# Schamatic.net
KiCad netlist of a schematic drawn in EAGLE
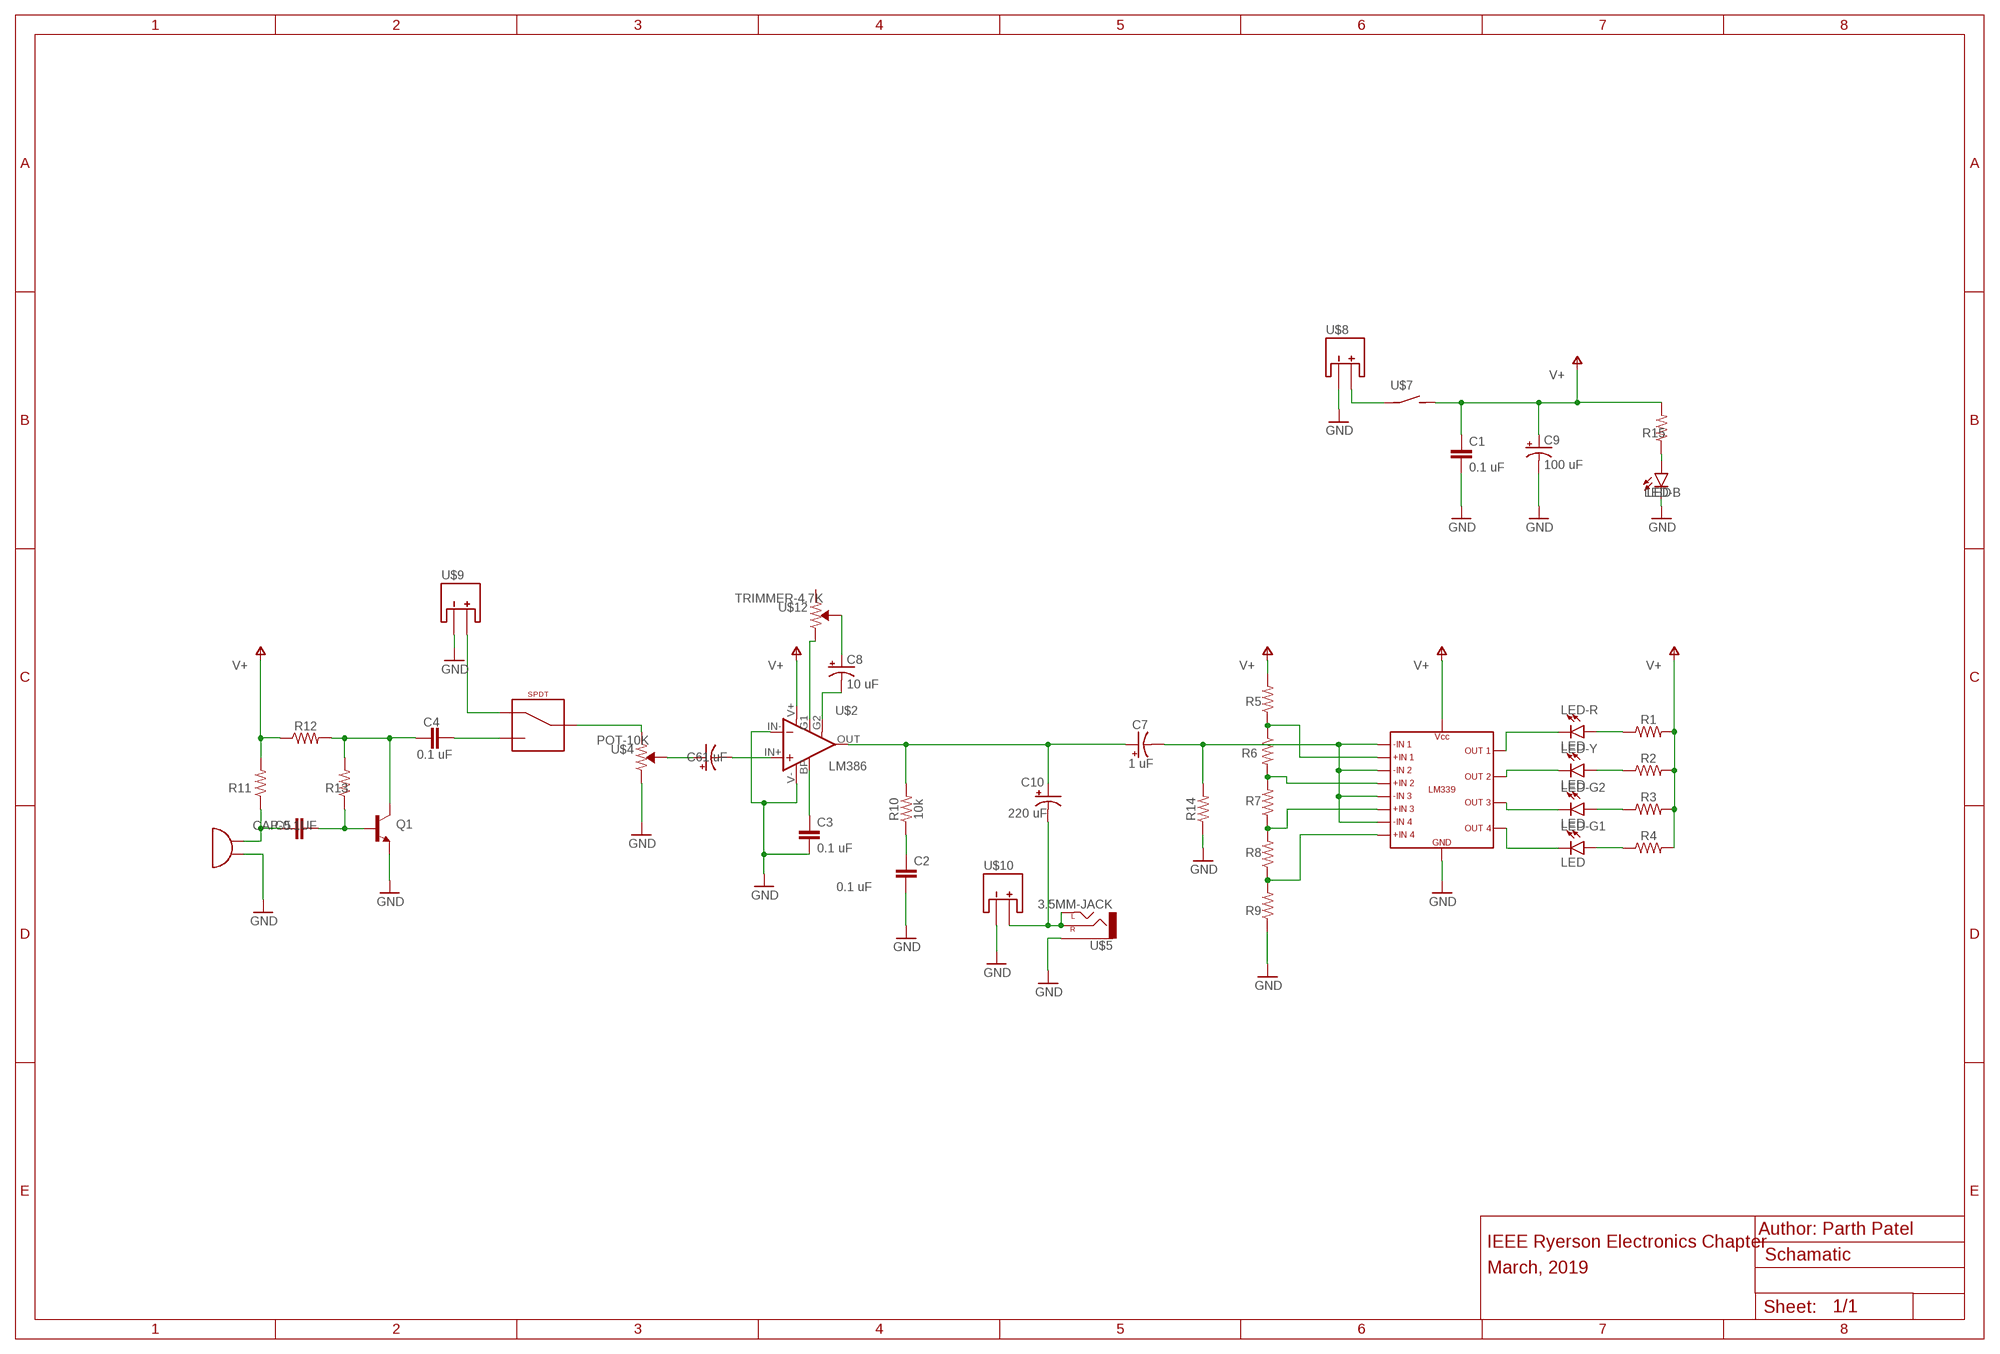
[diagram p0: schematic, sheet 1]

(export (version "E")
  (design (tool "Eeschema 10.0.6"))
  (components
    (comp (ref "C1")
      (value "0.1 uF")
      (footprint "eagle-import:CAP-PTH-SMALL-KIT")
      (libsource (lib "eagle-import") (part "CAP-0.1UF"))
    )
    (comp (ref "C2")
      (value "0.1 uF")
      (footprint "eagle-import:CAP-PTH-SMALL-KIT")
      (libsource (lib "eagle-import") (part "CAP-0.1UF"))
    )
    (comp (ref "C3")
      (value "0.1 uF")
      (footprint "eagle-import:CAP-PTH-SMALL-KIT")
      (libsource (lib "eagle-import") (part "CAP-0.1UF"))
    )
    (comp (ref "C4")
      (value "0.1 uF")
      (footprint "eagle-import:CAP-PTH-SMALL-KIT")
      (libsource (lib "eagle-import") (part "CAP-0.1UF"))
    )
    (comp (ref "C5")
      (value "CAP-0.1UF")
      (footprint "eagle-import:CAP-PTH-SMALL-KIT")
      (libsource (lib "eagle-import") (part "CAP-0.1UF"))
    )
    (comp (ref "C6")
      (value "1 uF")
      (footprint "eagle-import:CPOL-RADIAL-2.5MM-5.2MM")
      (libsource (lib "eagle-import") (part "CAP-1UF"))
    )
    (comp (ref "C7")
      (value "1 uF")
      (footprint "eagle-import:CPOL-RADIAL-2.5MM-5.2MM")
      (libsource (lib "eagle-import") (part "CAP-1UF"))
    )
    (comp (ref "C8")
      (value "10 uF")
      (footprint "eagle-import:CPOL-RADIAL-2.5MM-5.2MM")
      (libsource (lib "eagle-import") (part "CAP-10UF"))
    )
    (comp (ref "C9")
      (value "100 uF")
      (footprint "eagle-import:CPOL-RADIAL-2.5MM-6.5MM")
      (libsource (lib "eagle-import") (part "CAP-100UF"))
    )
    (comp (ref "C10")
      (value "220 uF")
      (footprint "eagle-import:CPOL-RADIAL-2.5MM-8.1MM")
      (libsource (lib "eagle-import") (part "CAP-220UF"))
    )
    (comp (ref "LED-B")
      (value "LED")
      (footprint "eagle-import:LED_5MM-KIT")
      (libsource (lib "eagle-import") (part "LED"))
    )
    (comp (ref "LED-G1")
      (value "LED")
      (footprint "eagle-import:LED_5MM-KIT")
      (libsource (lib "eagle-import") (part "LED"))
    )
    (comp (ref "LED-G2")
      (value "LED")
      (footprint "eagle-import:LED_5MM-KIT")
      (libsource (lib "eagle-import") (part "LED"))
    )
    (comp (ref "LED-R")
      (value "LED")
      (footprint "eagle-import:LED_5MM-KIT")
      (libsource (lib "eagle-import") (part "LED"))
    )
    (comp (ref "LED-Y")
      (value "LED")
      (footprint "eagle-import:LED_5MM-KIT")
      (libsource (lib "eagle-import") (part "LED"))
    )
    (comp (ref "Q1")
      (value "2N3904")
      (footprint "eagle-import:TO92-CBE")
      (libsource (lib "eagle-import") (part "2N3904"))
    )
    (comp (ref "R1")
      (value "470")
      (footprint "eagle-import:AXIAL-0.3-KIT")
      (libsource (lib "eagle-import") (part "RESISTOR"))
    )
    (comp (ref "R2")
      (value "RESISTOR")
      (footprint "eagle-import:AXIAL-0.3-KIT")
      (libsource (lib "eagle-import") (part "RESISTOR"))
    )
    (comp (ref "R3")
      (value "RESISTOR")
      (footprint "eagle-import:AXIAL-0.3-KIT")
      (libsource (lib "eagle-import") (part "RESISTOR"))
    )
    (comp (ref "R4")
      (value "RESISTOR")
      (footprint "eagle-import:AXIAL-0.3-KIT")
      (libsource (lib "eagle-import") (part "RESISTOR"))
    )
    (comp (ref "R5")
      (value "RESISTOR")
      (footprint "eagle-import:AXIAL-0.3-KIT")
      (libsource (lib "eagle-import") (part "RESISTOR"))
    )
    (comp (ref "R6")
      (value "RESISTOR")
      (footprint "eagle-import:AXIAL-0.3-KIT")
      (libsource (lib "eagle-import") (part "RESISTOR"))
    )
    (comp (ref "R7")
      (value "RESISTOR")
      (footprint "eagle-import:AXIAL-0.3-KIT")
      (libsource (lib "eagle-import") (part "RESISTOR"))
    )
    (comp (ref "R8")
      (value "RESISTOR")
      (footprint "eagle-import:AXIAL-0.3-KIT")
      (libsource (lib "eagle-import") (part "RESISTOR"))
    )
    (comp (ref "R9")
      (value "RESISTOR")
      (footprint "eagle-import:AXIAL-0.3-KIT")
      (libsource (lib "eagle-import") (part "RESISTOR"))
    )
    (comp (ref "R10")
      (value "10k")
      (footprint "eagle-import:AXIAL-0.3-KIT")
      (libsource (lib "eagle-import") (part "RESISTOR"))
    )
    (comp (ref "R11")
      (value "RESISTOR")
      (footprint "eagle-import:AXIAL-0.3-KIT")
      (libsource (lib "eagle-import") (part "RESISTOR"))
    )
    (comp (ref "R12")
      (value "RESISTOR")
      (footprint "eagle-import:AXIAL-0.3-KIT")
      (libsource (lib "eagle-import") (part "RESISTOR"))
    )
    (comp (ref "R13")
      (value "RESISTOR")
      (footprint "eagle-import:AXIAL-0.3-KIT")
      (libsource (lib "eagle-import") (part "RESISTOR"))
    )
    (comp (ref "R14")
      (value "RESISTOR")
      (footprint "eagle-import:AXIAL-0.3-KIT")
      (libsource (lib "eagle-import") (part "RESISTOR"))
    )
    (comp (ref "R15")
      (value "RESISTOR")
      (footprint "eagle-import:AXIAL-0.3-KIT")
      (libsource (lib "eagle-import") (part "RESISTOR"))
    )
    (comp (ref "U$1")
      (value "SPDT")
      (footprint "eagle-import:OS102011MA1QN1")
      (libsource (lib "eagle-import") (part "SPDT"))
    )
    (comp (ref "U$2")
      (value "LM386")
      (footprint "eagle-import:DIL08")
      (libsource (lib "eagle-import") (part "LM386"))
    )
    (comp (ref "U$3")
      (value "LM339")
      (footprint "eagle-import:DIL14")
      (libsource (lib "eagle-import") (part "LM339"))
    )
    (comp (ref "U$4")
      (value "POT-10K")
      (footprint "eagle-import:PTV09-SERIES")
      (libsource (lib "eagle-import") (part "POT-10K"))
    )
    (comp (ref "U$5")
      (value "3.5MM-JACK")
      (footprint "eagle-import:SJ1-352XN")
      (libsource (lib "eagle-import") (part "3.5MM-JACK"))
    )
    (comp (ref "U$6")
      (value "MIC")
      (footprint "eagle-import:MIC")
      (libsource (lib "eagle-import") (part "MIC"))
    )
    (comp (ref "U$7")
      (value "SPST")
      (footprint "eagle-import:TMS6T1B1M1QE")
      (libsource (lib "eagle-import") (part "SPST"))
    )
    (comp (ref "U$8")
      (value "2PIN-CONNECTOR")
      (footprint "eagle-import:2PIN-CONN")
      (libsource (lib "eagle-import") (part "2PIN-CONNECTOR"))
    )
    (comp (ref "U$9")
      (value "2PIN-CONNECTOR")
      (footprint "eagle-import:2PIN-CONN")
      (libsource (lib "eagle-import") (part "2PIN-CONNECTOR"))
    )
    (comp (ref "U$10")
      (value "2PIN-CONNECTOR")
      (footprint "eagle-import:2PIN-CONN")
      (libsource (lib "eagle-import") (part "2PIN-CONNECTOR"))
    )
    (comp (ref "U$12")
      (value "TRIMMER-4.7K")
      (footprint "eagle-import:CB10MV472ME")
      (libsource (lib "eagle-import") (part "TRIMMER-4.7K"))
    )
  )
  (nets
    (net (code "1") (name "GND") (class "Default")
      (node (ref "C1") (pin "2") (pinfunction "2_2") (pintype "passive"))
      (node (ref "C2") (pin "2") (pinfunction "2_2") (pintype "passive"))
      (node (ref "C3") (pin "2") (pinfunction "2_2") (pintype "passive"))
      (node (ref "C9") (pin "-") (pinfunction "-_-") (pintype "passive"))
      (node (ref "LED-B") (pin "-") (pinfunction "C_-") (pintype "passive"))
      (node (ref "Q1") (pin "E") (pinfunction "E_E") (pintype "passive"))
      (node (ref "R14") (pin "P$1") (pinfunction "1_P$1") (pintype "passive"))
      (node (ref "R9") (pin "P$1") (pinfunction "1_P$1") (pintype "passive"))
      (node (ref "U$10") (pin "-") (pinfunction "-_-") (pintype "bidirectional"))
      (node (ref "U$2") (pin "IN-") (pinfunction "-IN_IN-") (pintype "input"))
      (node (ref "U$2") (pin "V-") (pinfunction "V-_V-") (pintype "power_in"))
      (node (ref "U$3") (pin "P$12") (pinfunction "P12_P$12") (pintype "bidirectional"))
      (node (ref "U$4") (pin "P$3") (pinfunction "CW_P$3") (pintype "passive"))
      (node (ref "U$5") (pin "P$1") (pinfunction "SLEEVE_P$1") (pintype "bidirectional"))
      (node (ref "U$6") (pin "-") (pinfunction "P$1_-") (pintype "bidirectional"))
      (node (ref "U$8") (pin "-") (pinfunction "-_-") (pintype "bidirectional"))
      (node (ref "U$9") (pin "-") (pinfunction "-_-") (pintype "bidirectional"))
    )
    (net (code "2") (name "Net-(C3-Pad1)") (class "Default")
      (node (ref "C3") (pin "1") (pinfunction "1_1") (pintype "passive"))
      (node (ref "U$2") (pin "BP") (pinfunction "BP_BP") (pintype "bidirectional"))
    )
    (net (code "3") (name "Net-(C4-Pad2)") (class "Default")
      (node (ref "C4") (pin "2") (pinfunction "2_2") (pintype "passive"))
      (node (ref "U$1") (pin "P$3") (pinfunction "P$3_P$3") (pintype "bidirectional"))
    )
    (net (code "4") (name "Net-(C8-Pad-)") (class "Default")
      (node (ref "C8") (pin "-") (pinfunction "-_-") (pintype "passive"))
      (node (ref "U$2") (pin "G2") (pinfunction "GAIN_G2") (pintype "bidirectional"))
    )
    (net (code "5") (name "Net-(LED-B-A)") (class "Default")
      (node (ref "LED-B") (pin "+") (pinfunction "A_+") (pintype "passive"))
      (node (ref "R15") (pin "P$1") (pinfunction "1_P$1") (pintype "passive"))
    )
    (net (code "6") (name "Net-(LED-G1-A)") (class "Default")
      (node (ref "LED-G1") (pin "+") (pinfunction "A_+") (pintype "passive"))
      (node (ref "R4") (pin "P$1") (pinfunction "1_P$1") (pintype "passive"))
    )
    (net (code "7") (name "Net-(LED-G1-C)") (class "Default")
      (node (ref "LED-G1") (pin "-") (pinfunction "C_-") (pintype "passive"))
      (node (ref "U$3") (pin "P$13") (pinfunction "P13_P$13") (pintype "bidirectional"))
    )
    (net (code "8") (name "Net-(LED-G2-A)") (class "Default")
      (node (ref "LED-G2") (pin "+") (pinfunction "A_+") (pintype "passive"))
      (node (ref "R3") (pin "P$1") (pinfunction "1_P$1") (pintype "passive"))
    )
    (net (code "9") (name "Net-(LED-G2-C)") (class "Default")
      (node (ref "LED-G2") (pin "-") (pinfunction "C_-") (pintype "passive"))
      (node (ref "U$3") (pin "P$14") (pinfunction "P14_P$14") (pintype "bidirectional"))
    )
    (net (code "10") (name "Net-(LED-R-A)") (class "Default")
      (node (ref "LED-R") (pin "+") (pinfunction "A_+") (pintype "passive"))
      (node (ref "R1") (pin "P$1") (pinfunction "1_P$1") (pintype "passive"))
    )
    (net (code "11") (name "Net-(LED-R-C)") (class "Default")
      (node (ref "LED-R") (pin "-") (pinfunction "C_-") (pintype "passive"))
      (node (ref "U$3") (pin "P$1") (pinfunction "P1_P$1") (pintype "bidirectional"))
    )
    (net (code "12") (name "Net-(LED-Y-A)") (class "Default")
      (node (ref "LED-Y") (pin "+") (pinfunction "A_+") (pintype "passive"))
      (node (ref "R2") (pin "P$1") (pinfunction "1_P$1") (pintype "passive"))
    )
    (net (code "13") (name "Net-(LED-Y-C)") (class "Default")
      (node (ref "LED-Y") (pin "-") (pinfunction "C_-") (pintype "passive"))
      (node (ref "U$3") (pin "P$2") (pinfunction "P2_P$2") (pintype "bidirectional"))
    )
    (net (code "14") (name "Net-(R5-1)") (class "Default")
      (node (ref "R5") (pin "P$1") (pinfunction "1_P$1") (pintype "passive"))
      (node (ref "R6") (pin "P$1") (pinfunction "1_P$1") (pintype "passive"))
      (node (ref "U$3") (pin "P$7") (pinfunction "P7_P$7") (pintype "bidirectional"))
    )
    (net (code "15") (name "Net-(R6-2)") (class "Default")
      (node (ref "R6") (pin "P$2") (pinfunction "2_P$2") (pintype "passive"))
      (node (ref "R7") (pin "P$2") (pinfunction "2_P$2") (pintype "passive"))
      (node (ref "U$3") (pin "P$5") (pinfunction "P5_P$5") (pintype "bidirectional"))
    )
    (net (code "16") (name "Net-(R7-1)") (class "Default")
      (node (ref "R7") (pin "P$1") (pinfunction "1_P$1") (pintype "passive"))
      (node (ref "R8") (pin "P$2") (pinfunction "2_P$2") (pintype "passive"))
      (node (ref "U$3") (pin "P$9") (pinfunction "P9_P$9") (pintype "bidirectional"))
    )
    (net (code "17") (name "Net-(R8-1)") (class "Default")
      (node (ref "R8") (pin "P$1") (pinfunction "1_P$1") (pintype "passive"))
      (node (ref "R9") (pin "P$2") (pinfunction "2_P$2") (pintype "passive"))
      (node (ref "U$3") (pin "P$11") (pinfunction "P11_P$11") (pintype "bidirectional"))
    )
    (net (code "18") (name "Net-(R10-1)") (class "Default")
      (node (ref "C2") (pin "1") (pinfunction "1_1") (pintype "passive"))
      (node (ref "R10") (pin "P$1") (pinfunction "1_P$1") (pintype "passive"))
    )
    (net (code "19") (name "Net-(R10-2)") (class "Default")
      (node (ref "C10") (pin "+") (pinfunction "+_+") (pintype "passive"))
      (node (ref "C7") (pin "+") (pinfunction "+_+") (pintype "passive"))
      (node (ref "R10") (pin "P$2") (pinfunction "2_P$2") (pintype "passive"))
      (node (ref "U$2") (pin "OUT") (pinfunction "OUT_OUT") (pintype "output"))
    )
    (net (code "20") (name "Net-(R11-1)") (class "Default")
      (node (ref "C5") (pin "1") (pinfunction "1_1") (pintype "passive"))
      (node (ref "R11") (pin "P$1") (pinfunction "1_P$1") (pintype "passive"))
      (node (ref "U$6") (pin "+") (pinfunction "P$2_+") (pintype "bidirectional"))
    )
    (net (code "21") (name "Net-(R12-2)") (class "Default")
      (node (ref "C4") (pin "1") (pinfunction "1_1") (pintype "passive"))
      (node (ref "Q1") (pin "C") (pinfunction "C_C") (pintype "passive"))
      (node (ref "R12") (pin "P$2") (pinfunction "2_P$2") (pintype "passive"))
      (node (ref "R13") (pin "P$2") (pinfunction "2_P$2") (pintype "passive"))
    )
    (net (code "22") (name "Net-(R13-1)") (class "Default")
      (node (ref "C5") (pin "2") (pinfunction "2_2") (pintype "passive"))
      (node (ref "Q1") (pin "B") (pinfunction "B_B") (pintype "passive"))
      (node (ref "R13") (pin "P$1") (pinfunction "1_P$1") (pintype "passive"))
    )
    (net (code "23") (name "Net-(R14-2)") (class "Default")
      (node (ref "C7") (pin "-") (pinfunction "-_-") (pintype "passive"))
      (node (ref "R14") (pin "P$2") (pinfunction "2_P$2") (pintype "passive"))
      (node (ref "U$3") (pin "P$10") (pinfunction "P10_P$10") (pintype "bidirectional"))
      (node (ref "U$3") (pin "P$4") (pinfunction "P4_P$4") (pintype "bidirectional"))
      (node (ref "U$3") (pin "P$6") (pinfunction "P6_P$6") (pintype "bidirectional"))
      (node (ref "U$3") (pin "P$8") (pinfunction "P8_P$8") (pintype "bidirectional"))
    )
    (net (code "24") (name "Net-(U$1-PadP$1)") (class "Default")
      (node (ref "U$1") (pin "P$1") (pinfunction "P$1_P$1") (pintype "bidirectional"))
      (node (ref "U$9") (pin "+") (pinfunction "+_+") (pintype "bidirectional"))
    )
    (net (code "25") (name "Net-(U$2-+IN)") (class "Default")
      (node (ref "C6") (pin "-") (pinfunction "-_-") (pintype "passive"))
      (node (ref "U$2") (pin "IN+") (pinfunction "+IN_IN+") (pintype "input"))
    )
    (net (code "26") (name "Net-(U$4-CCW)") (class "Default")
      (node (ref "U$1") (pin "P$2") (pinfunction "P$2_P$2") (pintype "bidirectional"))
      (node (ref "U$4") (pin "P$1") (pinfunction "CCW_P$1") (pintype "passive"))
    )
    (net (code "27") (name "Net-(U$4-WIPER)") (class "Default")
      (node (ref "C6") (pin "+") (pinfunction "+_+") (pintype "passive"))
      (node (ref "U$4") (pin "P$2") (pinfunction "WIPER_P$2") (pintype "passive"))
    )
    (net (code "28") (name "Net-(U$5-LEFT)") (class "Default")
      (node (ref "C10") (pin "-") (pinfunction "-_-") (pintype "passive"))
      (node (ref "U$10") (pin "+") (pinfunction "+_+") (pintype "bidirectional"))
      (node (ref "U$5") (pin "P$2") (pinfunction "RIGHT_P$2") (pintype "bidirectional"))
      (node (ref "U$5") (pin "P$3") (pinfunction "LEFT_P$3") (pintype "bidirectional"))
    )
    (net (code "29") (name "Net-(U$7-P)") (class "Default")
      (node (ref "U$7") (pin "+") (pinfunction "P_+") (pintype "passive"))
      (node (ref "U$8") (pin "+") (pinfunction "+_+") (pintype "bidirectional"))
    )
    (net (code "30") (name "Net-(U$12-CW)") (class "Default")
      (node (ref "U$12") (pin "P$3") (pinfunction "CW_P$3") (pintype "passive"))
      (node (ref "U$2") (pin "G1") (pinfunction "GAIN_G1") (pintype "bidirectional"))
    )
    (net (code "31") (name "Net-(U$12-WIPER)") (class "Default")
      (node (ref "C8") (pin "+") (pinfunction "+_+") (pintype "passive"))
      (node (ref "U$12") (pin "P$2") (pinfunction "WIPER_P$2") (pintype "passive"))
    )
    (net (code "32") (name "V+") (class "Default")
      (node (ref "C1") (pin "1") (pinfunction "1_1") (pintype "passive"))
      (node (ref "C9") (pin "+") (pinfunction "+_+") (pintype "passive"))
      (node (ref "R1") (pin "P$2") (pinfunction "2_P$2") (pintype "passive"))
      (node (ref "R11") (pin "P$2") (pinfunction "2_P$2") (pintype "passive"))
      (node (ref "R12") (pin "P$1") (pinfunction "1_P$1") (pintype "passive"))
      (node (ref "R15") (pin "P$2") (pinfunction "2_P$2") (pintype "passive"))
      (node (ref "R2") (pin "P$2") (pinfunction "2_P$2") (pintype "passive"))
      (node (ref "R3") (pin "P$2") (pinfunction "2_P$2") (pintype "passive"))
      (node (ref "R4") (pin "P$2") (pinfunction "2_P$2") (pintype "passive"))
      (node (ref "R5") (pin "P$2") (pinfunction "2_P$2") (pintype "passive"))
      (node (ref "U$2") (pin "V+") (pinfunction "V+_V+") (pintype "power_in"))
      (node (ref "U$3") (pin "P$3") (pinfunction "P3_P$3") (pintype "bidirectional"))
      (node (ref "U$7") (pin "-") (pinfunction "S_-") (pintype "passive"))
    )
    (net (code "33") (name "unconnected-(U$12-CCW-PadP$1)") (class "Default")
      (node (ref "U$12") (pin "P$1") (pinfunction "CCW_P$1") (pintype "passive"))
    )
  )
)
